# debug-leds.net
KiCad netlist of a schematic drawn in EAGLE
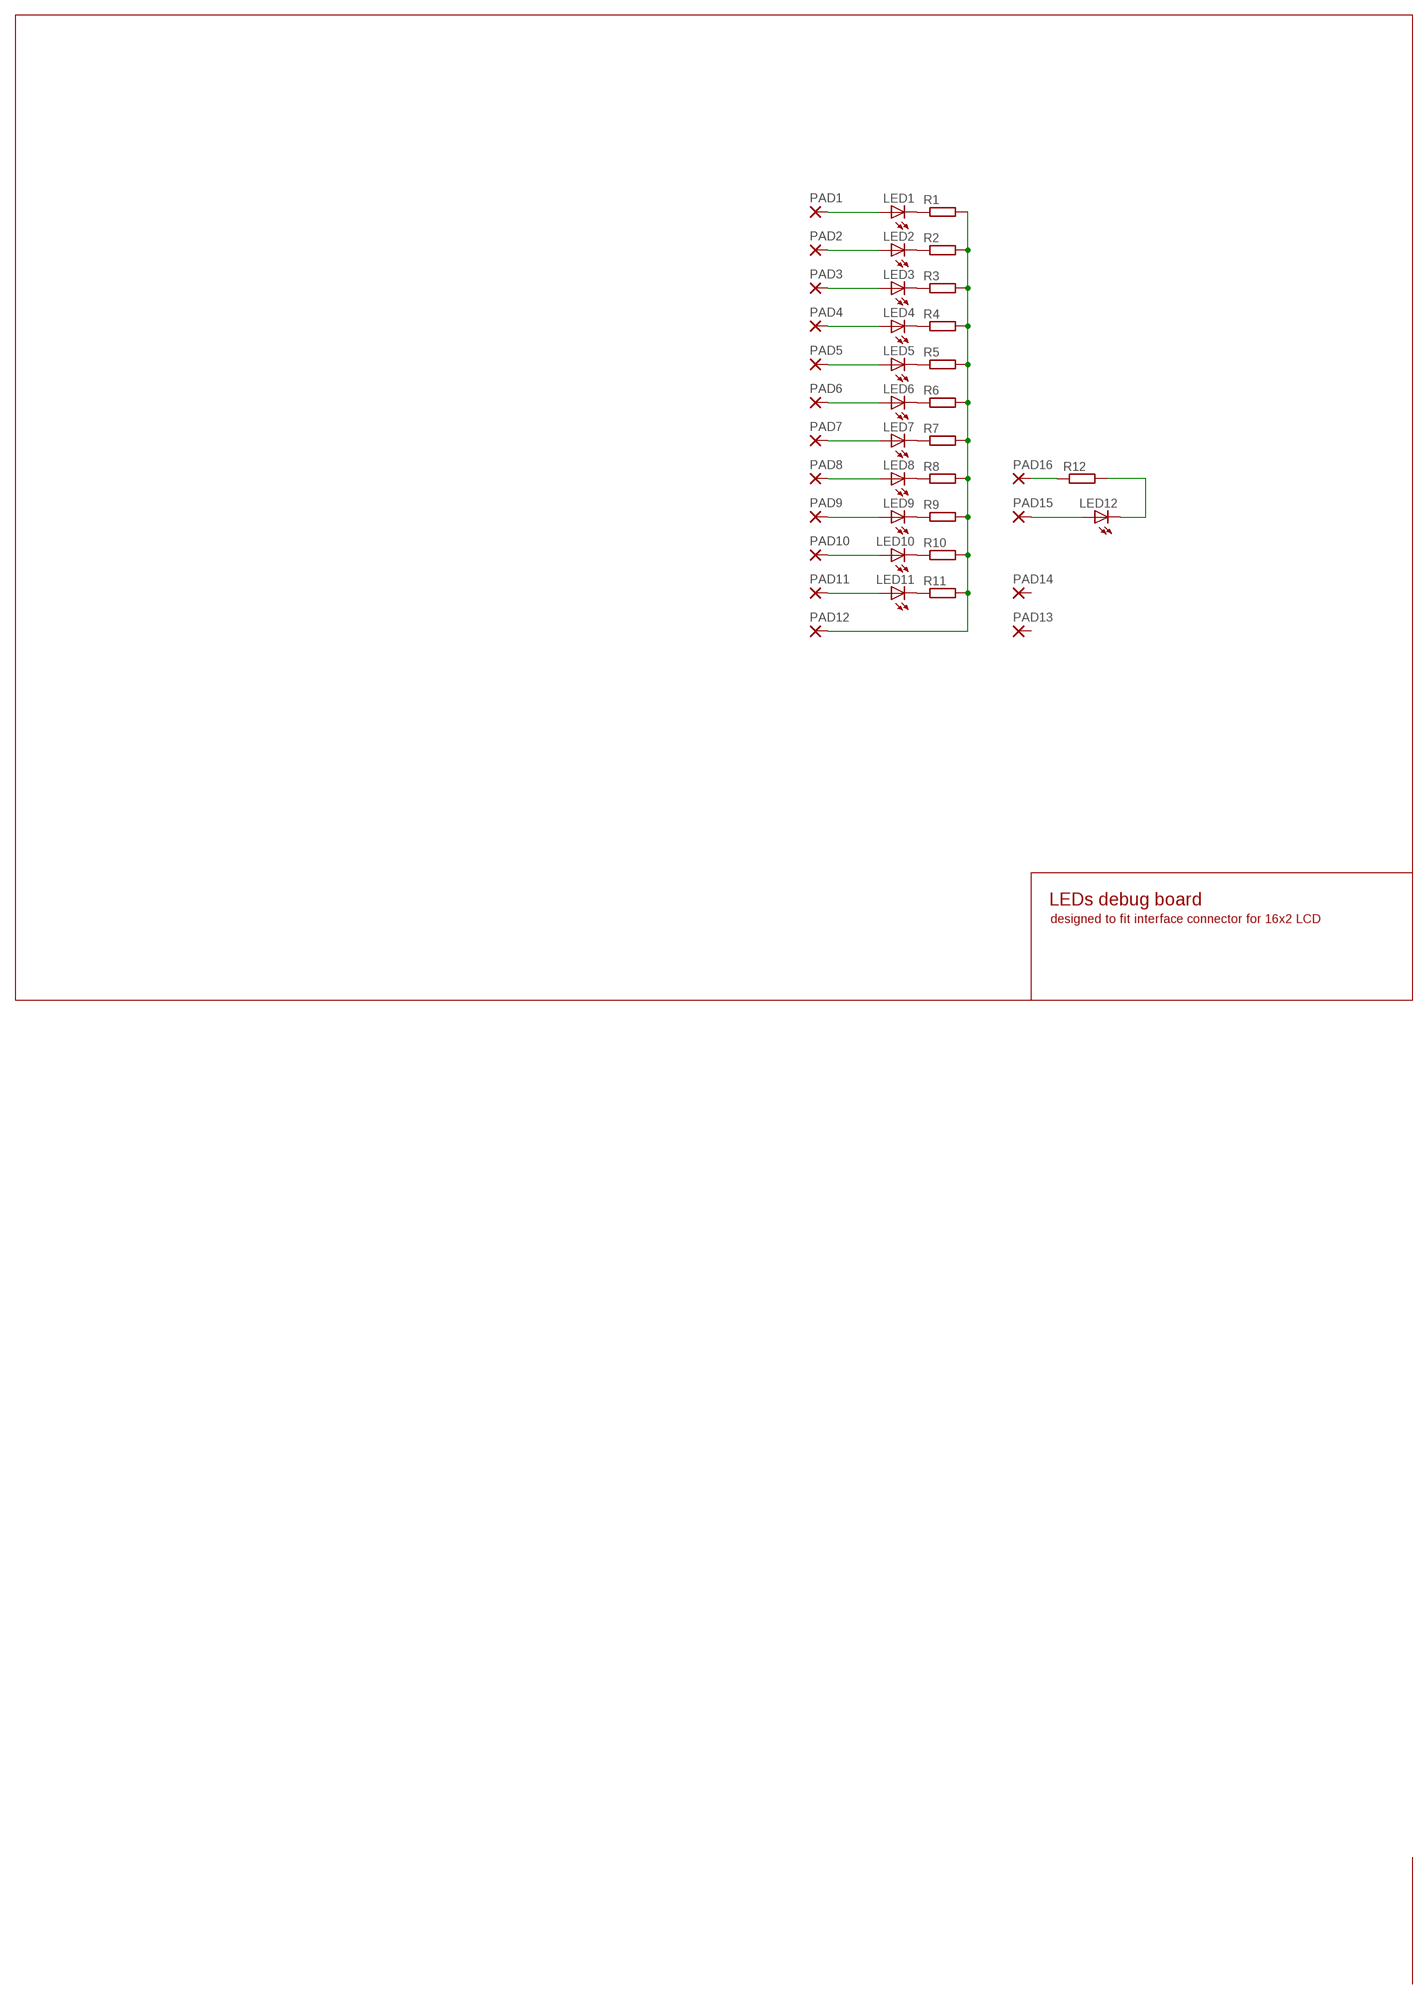
[diagram p0: schematic, sheet 1]

(export (version "E")
  (design (tool "Eeschema 10.0.6"))
  (components
    (comp (ref "LED1")
      (value "LEDSML0805")
      (footprint "eagle-import:SML0805")
      (libsource (lib "eagle-import") (part "LEDSML0805"))
    )
    (comp (ref "LED2")
      (value "LEDSML0805")
      (footprint "eagle-import:SML0805")
      (libsource (lib "eagle-import") (part "LEDSML0805"))
    )
    (comp (ref "LED3")
      (value "LEDSML0805")
      (footprint "eagle-import:SML0805")
      (libsource (lib "eagle-import") (part "LEDSML0805"))
    )
    (comp (ref "LED4")
      (value "LEDSML0805")
      (footprint "eagle-import:SML0805")
      (libsource (lib "eagle-import") (part "LEDSML0805"))
    )
    (comp (ref "LED5")
      (value "LEDSML0805")
      (footprint "eagle-import:SML0805")
      (libsource (lib "eagle-import") (part "LEDSML0805"))
    )
    (comp (ref "LED6")
      (value "LEDSML0805")
      (footprint "eagle-import:SML0805")
      (libsource (lib "eagle-import") (part "LEDSML0805"))
    )
    (comp (ref "LED7")
      (value "LEDSML0805")
      (footprint "eagle-import:SML0805")
      (libsource (lib "eagle-import") (part "LEDSML0805"))
    )
    (comp (ref "LED8")
      (value "LEDSML0805")
      (footprint "eagle-import:SML0805")
      (libsource (lib "eagle-import") (part "LEDSML0805"))
    )
    (comp (ref "LED9")
      (value "LEDSML0805")
      (footprint "eagle-import:SML0805")
      (libsource (lib "eagle-import") (part "LEDSML0805"))
    )
    (comp (ref "LED10")
      (value "LEDSML0805")
      (footprint "eagle-import:SML0805")
      (libsource (lib "eagle-import") (part "LEDSML0805"))
    )
    (comp (ref "LED11")
      (value "LEDSML0805")
      (footprint "eagle-import:SML0805")
      (libsource (lib "eagle-import") (part "LEDSML0805"))
    )
    (comp (ref "LED12")
      (value "LEDSML0805")
      (footprint "eagle-import:SML0805")
      (libsource (lib "eagle-import") (part "LEDSML0805"))
    )
    (comp (ref "PAD1")
      (value "1,6/0,8")
      (footprint "eagle-import:1,6_0,8")
      (libsource (lib "eagle-import") (part "1,6/0,8"))
    )
    (comp (ref "PAD2")
      (value "1,6/0,8")
      (footprint "eagle-import:1,6_0,8")
      (libsource (lib "eagle-import") (part "1,6/0,8"))
    )
    (comp (ref "PAD3")
      (value "1,6/0,8")
      (footprint "eagle-import:1,6_0,8")
      (libsource (lib "eagle-import") (part "1,6/0,8"))
    )
    (comp (ref "PAD4")
      (value "1,6/0,8")
      (footprint "eagle-import:1,6_0,8")
      (libsource (lib "eagle-import") (part "1,6/0,8"))
    )
    (comp (ref "PAD5")
      (value "1,6/0,8")
      (footprint "eagle-import:1,6_0,8")
      (libsource (lib "eagle-import") (part "1,6/0,8"))
    )
    (comp (ref "PAD6")
      (value "1,6/0,8")
      (footprint "eagle-import:1,6_0,8")
      (libsource (lib "eagle-import") (part "1,6/0,8"))
    )
    (comp (ref "PAD7")
      (value "1,6/0,8")
      (footprint "eagle-import:1,6_0,8")
      (libsource (lib "eagle-import") (part "1,6/0,8"))
    )
    (comp (ref "PAD8")
      (value "1,6/0,8")
      (footprint "eagle-import:1,6_0,8")
      (libsource (lib "eagle-import") (part "1,6/0,8"))
    )
    (comp (ref "PAD9")
      (value "1,6/0,8")
      (footprint "eagle-import:1,6_0,8")
      (libsource (lib "eagle-import") (part "1,6/0,8"))
    )
    (comp (ref "PAD10")
      (value "1,6/0,8")
      (footprint "eagle-import:1,6_0,8")
      (libsource (lib "eagle-import") (part "1,6/0,8"))
    )
    (comp (ref "PAD11")
      (value "1,6/0,8")
      (footprint "eagle-import:1,6_0,8")
      (libsource (lib "eagle-import") (part "1,6/0,8"))
    )
    (comp (ref "PAD12")
      (value "1,6/0,8")
      (footprint "eagle-import:1,6_0,8")
      (libsource (lib "eagle-import") (part "1,6/0,8"))
    )
    (comp (ref "PAD13")
      (value "1,6/0,8")
      (footprint "eagle-import:1,6_0,8")
      (libsource (lib "eagle-import") (part "1,6/0,8"))
    )
    (comp (ref "PAD14")
      (value "1,6/0,8")
      (footprint "eagle-import:1,6_0,8")
      (libsource (lib "eagle-import") (part "1,6/0,8"))
    )
    (comp (ref "PAD15")
      (value "1,6/0,8")
      (footprint "eagle-import:1,6_0,8")
      (libsource (lib "eagle-import") (part "1,6/0,8"))
    )
    (comp (ref "PAD16")
      (value "1,6/0,8")
      (footprint "eagle-import:1,6_0,8")
      (libsource (lib "eagle-import") (part "1,6/0,8"))
    )
    (comp (ref "R1")
      (value "R-EU_M0805")
      (footprint "eagle-import:M0805")
      (libsource (lib "eagle-import") (part "R-EU_M0805"))
    )
    (comp (ref "R2")
      (value "R-EU_M0805")
      (footprint "eagle-import:M0805")
      (libsource (lib "eagle-import") (part "R-EU_M0805"))
    )
    (comp (ref "R3")
      (value "R-EU_M0805")
      (footprint "eagle-import:M0805")
      (libsource (lib "eagle-import") (part "R-EU_M0805"))
    )
    (comp (ref "R4")
      (value "R-EU_M0805")
      (footprint "eagle-import:M0805")
      (libsource (lib "eagle-import") (part "R-EU_M0805"))
    )
    (comp (ref "R5")
      (value "R-EU_M0805")
      (footprint "eagle-import:M0805")
      (libsource (lib "eagle-import") (part "R-EU_M0805"))
    )
    (comp (ref "R6")
      (value "R-EU_M0805")
      (footprint "eagle-import:M0805")
      (libsource (lib "eagle-import") (part "R-EU_M0805"))
    )
    (comp (ref "R7")
      (value "R-EU_M0805")
      (footprint "eagle-import:M0805")
      (libsource (lib "eagle-import") (part "R-EU_M0805"))
    )
    (comp (ref "R8")
      (value "R-EU_M0805")
      (footprint "eagle-import:M0805")
      (libsource (lib "eagle-import") (part "R-EU_M0805"))
    )
    (comp (ref "R9")
      (value "R-EU_M0805")
      (footprint "eagle-import:M0805")
      (libsource (lib "eagle-import") (part "R-EU_M0805"))
    )
    (comp (ref "R10")
      (value "R-EU_M0805")
      (footprint "eagle-import:M0805")
      (libsource (lib "eagle-import") (part "R-EU_M0805"))
    )
    (comp (ref "R11")
      (value "R-EU_M0805")
      (footprint "eagle-import:M0805")
      (libsource (lib "eagle-import") (part "R-EU_M0805"))
    )
    (comp (ref "R12")
      (value "R-EU_M0805")
      (footprint "eagle-import:M0805")
      (libsource (lib "eagle-import") (part "R-EU_M0805"))
    )
  )
  (nets
    (net (code "1") (name "Net-(LED1-PadC)") (class "Default")
      (node (ref "LED1") (pin "C") (pinfunction "C_C") (pintype "passive"))
      (node (ref "R1") (pin "1") (pinfunction "1_1") (pintype "passive"))
    )
    (net (code "2") (name "Net-(LED2-PadC)") (class "Default")
      (node (ref "LED2") (pin "C") (pinfunction "C_C") (pintype "passive"))
      (node (ref "R2") (pin "1") (pinfunction "1_1") (pintype "passive"))
    )
    (net (code "3") (name "Net-(LED3-PadC)") (class "Default")
      (node (ref "LED3") (pin "C") (pinfunction "C_C") (pintype "passive"))
      (node (ref "R3") (pin "1") (pinfunction "1_1") (pintype "passive"))
    )
    (net (code "4") (name "Net-(LED4-PadC)") (class "Default")
      (node (ref "LED4") (pin "C") (pinfunction "C_C") (pintype "passive"))
      (node (ref "R4") (pin "1") (pinfunction "1_1") (pintype "passive"))
    )
    (net (code "5") (name "Net-(LED5-PadC)") (class "Default")
      (node (ref "LED5") (pin "C") (pinfunction "C_C") (pintype "passive"))
      (node (ref "R5") (pin "1") (pinfunction "1_1") (pintype "passive"))
    )
    (net (code "6") (name "Net-(LED6-PadC)") (class "Default")
      (node (ref "LED6") (pin "C") (pinfunction "C_C") (pintype "passive"))
      (node (ref "R6") (pin "1") (pinfunction "1_1") (pintype "passive"))
    )
    (net (code "7") (name "Net-(LED7-PadC)") (class "Default")
      (node (ref "LED7") (pin "C") (pinfunction "C_C") (pintype "passive"))
      (node (ref "R7") (pin "1") (pinfunction "1_1") (pintype "passive"))
    )
    (net (code "8") (name "Net-(LED8-PadC)") (class "Default")
      (node (ref "LED8") (pin "C") (pinfunction "C_C") (pintype "passive"))
      (node (ref "R8") (pin "1") (pinfunction "1_1") (pintype "passive"))
    )
    (net (code "9") (name "Net-(LED9-PadC)") (class "Default")
      (node (ref "LED9") (pin "C") (pinfunction "C_C") (pintype "passive"))
      (node (ref "R9") (pin "1") (pinfunction "1_1") (pintype "passive"))
    )
    (net (code "10") (name "Net-(LED10-PadC)") (class "Default")
      (node (ref "LED10") (pin "C") (pinfunction "C_C") (pintype "passive"))
      (node (ref "R10") (pin "1") (pinfunction "1_1") (pintype "passive"))
    )
    (net (code "11") (name "Net-(LED11-PadC)") (class "Default")
      (node (ref "LED11") (pin "C") (pinfunction "C_C") (pintype "passive"))
      (node (ref "R11") (pin "1") (pinfunction "1_1") (pintype "passive"))
    )
    (net (code "12") (name "Net-(LED12-PadC)") (class "Default")
      (node (ref "LED12") (pin "C") (pinfunction "C_C") (pintype "passive"))
      (node (ref "R12") (pin "2") (pinfunction "2_2") (pintype "passive"))
    )
    (net (code "13") (name "Net-(PAD1-P)") (class "Default")
      (node (ref "LED1") (pin "A") (pinfunction "A_A") (pintype "passive"))
      (node (ref "PAD1") (pin "1") (pinfunction "P_1") (pintype "passive"))
    )
    (net (code "14") (name "Net-(PAD2-P)") (class "Default")
      (node (ref "LED2") (pin "A") (pinfunction "A_A") (pintype "passive"))
      (node (ref "PAD2") (pin "1") (pinfunction "P_1") (pintype "passive"))
    )
    (net (code "15") (name "Net-(PAD3-P)") (class "Default")
      (node (ref "LED3") (pin "A") (pinfunction "A_A") (pintype "passive"))
      (node (ref "PAD3") (pin "1") (pinfunction "P_1") (pintype "passive"))
    )
    (net (code "16") (name "Net-(PAD4-P)") (class "Default")
      (node (ref "LED4") (pin "A") (pinfunction "A_A") (pintype "passive"))
      (node (ref "PAD4") (pin "1") (pinfunction "P_1") (pintype "passive"))
    )
    (net (code "17") (name "Net-(PAD5-P)") (class "Default")
      (node (ref "LED5") (pin "A") (pinfunction "A_A") (pintype "passive"))
      (node (ref "PAD5") (pin "1") (pinfunction "P_1") (pintype "passive"))
    )
    (net (code "18") (name "Net-(PAD6-P)") (class "Default")
      (node (ref "LED6") (pin "A") (pinfunction "A_A") (pintype "passive"))
      (node (ref "PAD6") (pin "1") (pinfunction "P_1") (pintype "passive"))
    )
    (net (code "19") (name "Net-(PAD7-P)") (class "Default")
      (node (ref "LED7") (pin "A") (pinfunction "A_A") (pintype "passive"))
      (node (ref "PAD7") (pin "1") (pinfunction "P_1") (pintype "passive"))
    )
    (net (code "20") (name "Net-(PAD8-P)") (class "Default")
      (node (ref "LED8") (pin "A") (pinfunction "A_A") (pintype "passive"))
      (node (ref "PAD8") (pin "1") (pinfunction "P_1") (pintype "passive"))
    )
    (net (code "21") (name "Net-(PAD9-P)") (class "Default")
      (node (ref "LED9") (pin "A") (pinfunction "A_A") (pintype "passive"))
      (node (ref "PAD9") (pin "1") (pinfunction "P_1") (pintype "passive"))
    )
    (net (code "22") (name "Net-(PAD10-P)") (class "Default")
      (node (ref "LED10") (pin "A") (pinfunction "A_A") (pintype "passive"))
      (node (ref "PAD10") (pin "1") (pinfunction "P_1") (pintype "passive"))
    )
    (net (code "23") (name "Net-(PAD11-P)") (class "Default")
      (node (ref "LED11") (pin "A") (pinfunction "A_A") (pintype "passive"))
      (node (ref "PAD11") (pin "1") (pinfunction "P_1") (pintype "passive"))
    )
    (net (code "24") (name "Net-(PAD12-P)") (class "Default")
      (node (ref "PAD12") (pin "1") (pinfunction "P_1") (pintype "passive"))
      (node (ref "R1") (pin "2") (pinfunction "2_2") (pintype "passive"))
      (node (ref "R10") (pin "2") (pinfunction "2_2") (pintype "passive"))
      (node (ref "R11") (pin "2") (pinfunction "2_2") (pintype "passive"))
      (node (ref "R2") (pin "2") (pinfunction "2_2") (pintype "passive"))
      (node (ref "R3") (pin "2") (pinfunction "2_2") (pintype "passive"))
      (node (ref "R4") (pin "2") (pinfunction "2_2") (pintype "passive"))
      (node (ref "R5") (pin "2") (pinfunction "2_2") (pintype "passive"))
      (node (ref "R6") (pin "2") (pinfunction "2_2") (pintype "passive"))
      (node (ref "R7") (pin "2") (pinfunction "2_2") (pintype "passive"))
      (node (ref "R8") (pin "2") (pinfunction "2_2") (pintype "passive"))
      (node (ref "R9") (pin "2") (pinfunction "2_2") (pintype "passive"))
    )
    (net (code "25") (name "Net-(PAD15-P)") (class "Default")
      (node (ref "LED12") (pin "A") (pinfunction "A_A") (pintype "passive"))
      (node (ref "PAD15") (pin "1") (pinfunction "P_1") (pintype "passive"))
    )
    (net (code "26") (name "Net-(PAD16-P)") (class "Default")
      (node (ref "PAD16") (pin "1") (pinfunction "P_1") (pintype "passive"))
      (node (ref "R12") (pin "1") (pinfunction "1_1") (pintype "passive"))
    )
    (net (code "27") (name "unconnected-(PAD13-P-Pad1)") (class "Default")
      (node (ref "PAD13") (pin "1") (pinfunction "P_1") (pintype "passive"))
    )
    (net (code "28") (name "unconnected-(PAD14-P-Pad1)") (class "Default")
      (node (ref "PAD14") (pin "1") (pinfunction "P_1") (pintype "passive"))
    )
  )
)
